# Frequency_Board.net
KiCad netlist of a schematic drawn in EAGLE
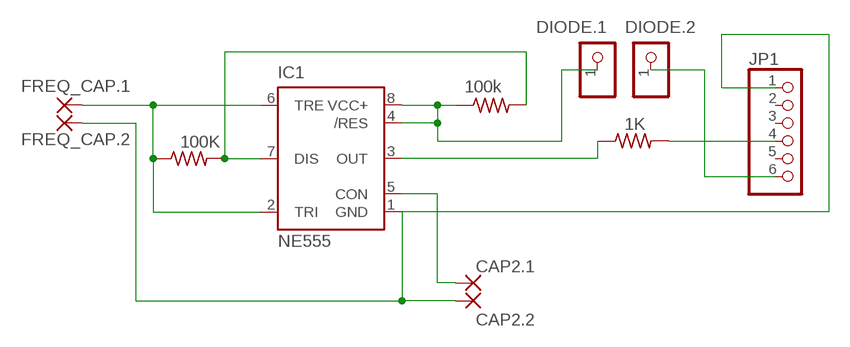
[diagram p0: schematic, sheet 1]

(export (version "E")
  (design (tool "Eeschema 10.0.6"))
  (components
    (comp (ref "1K")
      (value "R-US_0204/5")
      (footprint "eagle-import:0204_5")
      (libsource (lib "eagle-import") (part "R-US_0204/5"))
    )
    (comp (ref "100K")
      (value "R-US_0204/5")
      (footprint "eagle-import:0204_5")
      (libsource (lib "eagle-import") (part "R-US_0204/5"))
    )
    (comp (ref "CAP2.1")
      (value "1,6/0,8")
      (footprint "eagle-import:1,6_0,8")
      (libsource (lib "eagle-import") (part "1,6/0,8"))
    )
    (comp (ref "CAP2.2")
      (value "1,6/0,8")
      (footprint "eagle-import:1,6_0,8")
      (libsource (lib "eagle-import") (part "1,6/0,8"))
    )
    (comp (ref "DIODE.1")
      (value "PINHD-1X1")
      (footprint "eagle-import:1X01")
      (libsource (lib "eagle-import") (part "PINHD-1X1"))
    )
    (comp (ref "DIODE.2")
      (value "PINHD-1X1")
      (footprint "eagle-import:1X01")
      (libsource (lib "eagle-import") (part "PINHD-1X1"))
    )
    (comp (ref "FREQ_CAP.1")
      (value "1,6/0,8")
      (footprint "eagle-import:1,6_0,8")
      (libsource (lib "eagle-import") (part "1,6/0,8"))
    )
    (comp (ref "FREQ_CAP.2")
      (value "1,6/0,8")
      (footprint "eagle-import:1,6_0,8")
      (libsource (lib "eagle-import") (part "1,6/0,8"))
    )
    (comp (ref "IC1")
      (value "NE555")
      (footprint "eagle-import:DIL-08")
      (fields (field (name "MF") "Arrow Electronics") (field (name "MPN") "NE555N"))
      (libsource (lib "eagle-import") (part "NE555"))
    )
    (comp (ref "JP1")
      (value "PINHD-1X6")
      (footprint "eagle-import:1X06")
      (libsource (lib "eagle-import") (part "PINHD-1X6"))
    )
    (comp (ref "R1")
      (value "100k")
      (footprint "eagle-import:0204_5")
      (libsource (lib "eagle-import") (part "R-US_0204/5"))
    )
  )
  (nets
    (net (code "1") (name "Net-(1K-Pad2)") (class "Default")
      (node (ref "1K") (pin "2") (pinfunction "2_2") (pintype "passive"))
      (node (ref "JP1") (pin "4") (pinfunction "4_4") (pintype "passive"))
    )
    (net (code "2") (name "Net-(CAP2.1-P)") (class "Default")
      (node (ref "CAP2.1") (pin "1") (pinfunction "P_1") (pintype "passive"))
      (node (ref "IC1") (pin "5") (pinfunction "CON_5") (pintype "input"))
    )
    (net (code "3") (name "Net-(CAP2.2-P)") (class "Default")
      (node (ref "CAP2.2") (pin "1") (pinfunction "P_1") (pintype "passive"))
      (node (ref "FREQ_CAP.2") (pin "1") (pinfunction "P_1") (pintype "passive"))
      (node (ref "IC1") (pin "1") (pinfunction "GND_1") (pintype "power_in"))
      (node (ref "JP1") (pin "1") (pinfunction "1_1") (pintype "passive"))
    )
    (net (code "4") (name "Net-(DIODE.2-Pad1)") (class "Default")
      (node (ref "DIODE.2") (pin "1") (pinfunction "1_1") (pintype "passive"))
      (node (ref "JP1") (pin "6") (pinfunction "6_6") (pintype "passive"))
    )
    (net (code "5") (name "Net-(FREQ_CAP.1-P)") (class "Default")
      (node (ref "100K") (pin "1") (pinfunction "1_1") (pintype "passive"))
      (node (ref "FREQ_CAP.1") (pin "1") (pinfunction "P_1") (pintype "passive"))
      (node (ref "IC1") (pin "2") (pinfunction "TRI_2") (pintype "input"))
      (node (ref "IC1") (pin "6") (pinfunction "TRE_6") (pintype "input"))
    )
    (net (code "6") (name "Net-(IC1-DIS)") (class "Default")
      (node (ref "100K") (pin "2") (pinfunction "2_2") (pintype "passive"))
      (node (ref "IC1") (pin "7") (pinfunction "DIS_7") (pintype "input"))
      (node (ref "R1") (pin "2") (pinfunction "2_2") (pintype "passive"))
    )
    (net (code "7") (name "Net-(IC1-OUT)") (class "Default")
      (node (ref "1K") (pin "1") (pinfunction "1_1") (pintype "passive"))
      (node (ref "IC1") (pin "3") (pinfunction "OUT_3") (pintype "output"))
    )
    (net (code "8") (name "Net-(IC1-VCC+)") (class "Default")
      (node (ref "DIODE.1") (pin "1") (pinfunction "1_1") (pintype "passive"))
      (node (ref "IC1") (pin "4") (pinfunction "/RES_4") (pintype "input"))
      (node (ref "IC1") (pin "8") (pinfunction "VCC+_8") (pintype "power_in"))
      (node (ref "R1") (pin "1") (pinfunction "1_1") (pintype "passive"))
    )
    (net (code "9") (name "unconnected-(JP1-Pad2)") (class "Default")
      (node (ref "JP1") (pin "2") (pinfunction "2_2") (pintype "passive"))
    )
    (net (code "10") (name "unconnected-(JP1-Pad3)") (class "Default")
      (node (ref "JP1") (pin "3") (pinfunction "3_3") (pintype "passive"))
    )
    (net (code "11") (name "unconnected-(JP1-Pad5)") (class "Default")
      (node (ref "JP1") (pin "5") (pinfunction "5_5") (pintype "passive"))
    )
  )
)
